# DiplomScheme.net
KiCad netlist of a schematic drawn in Altium Designer
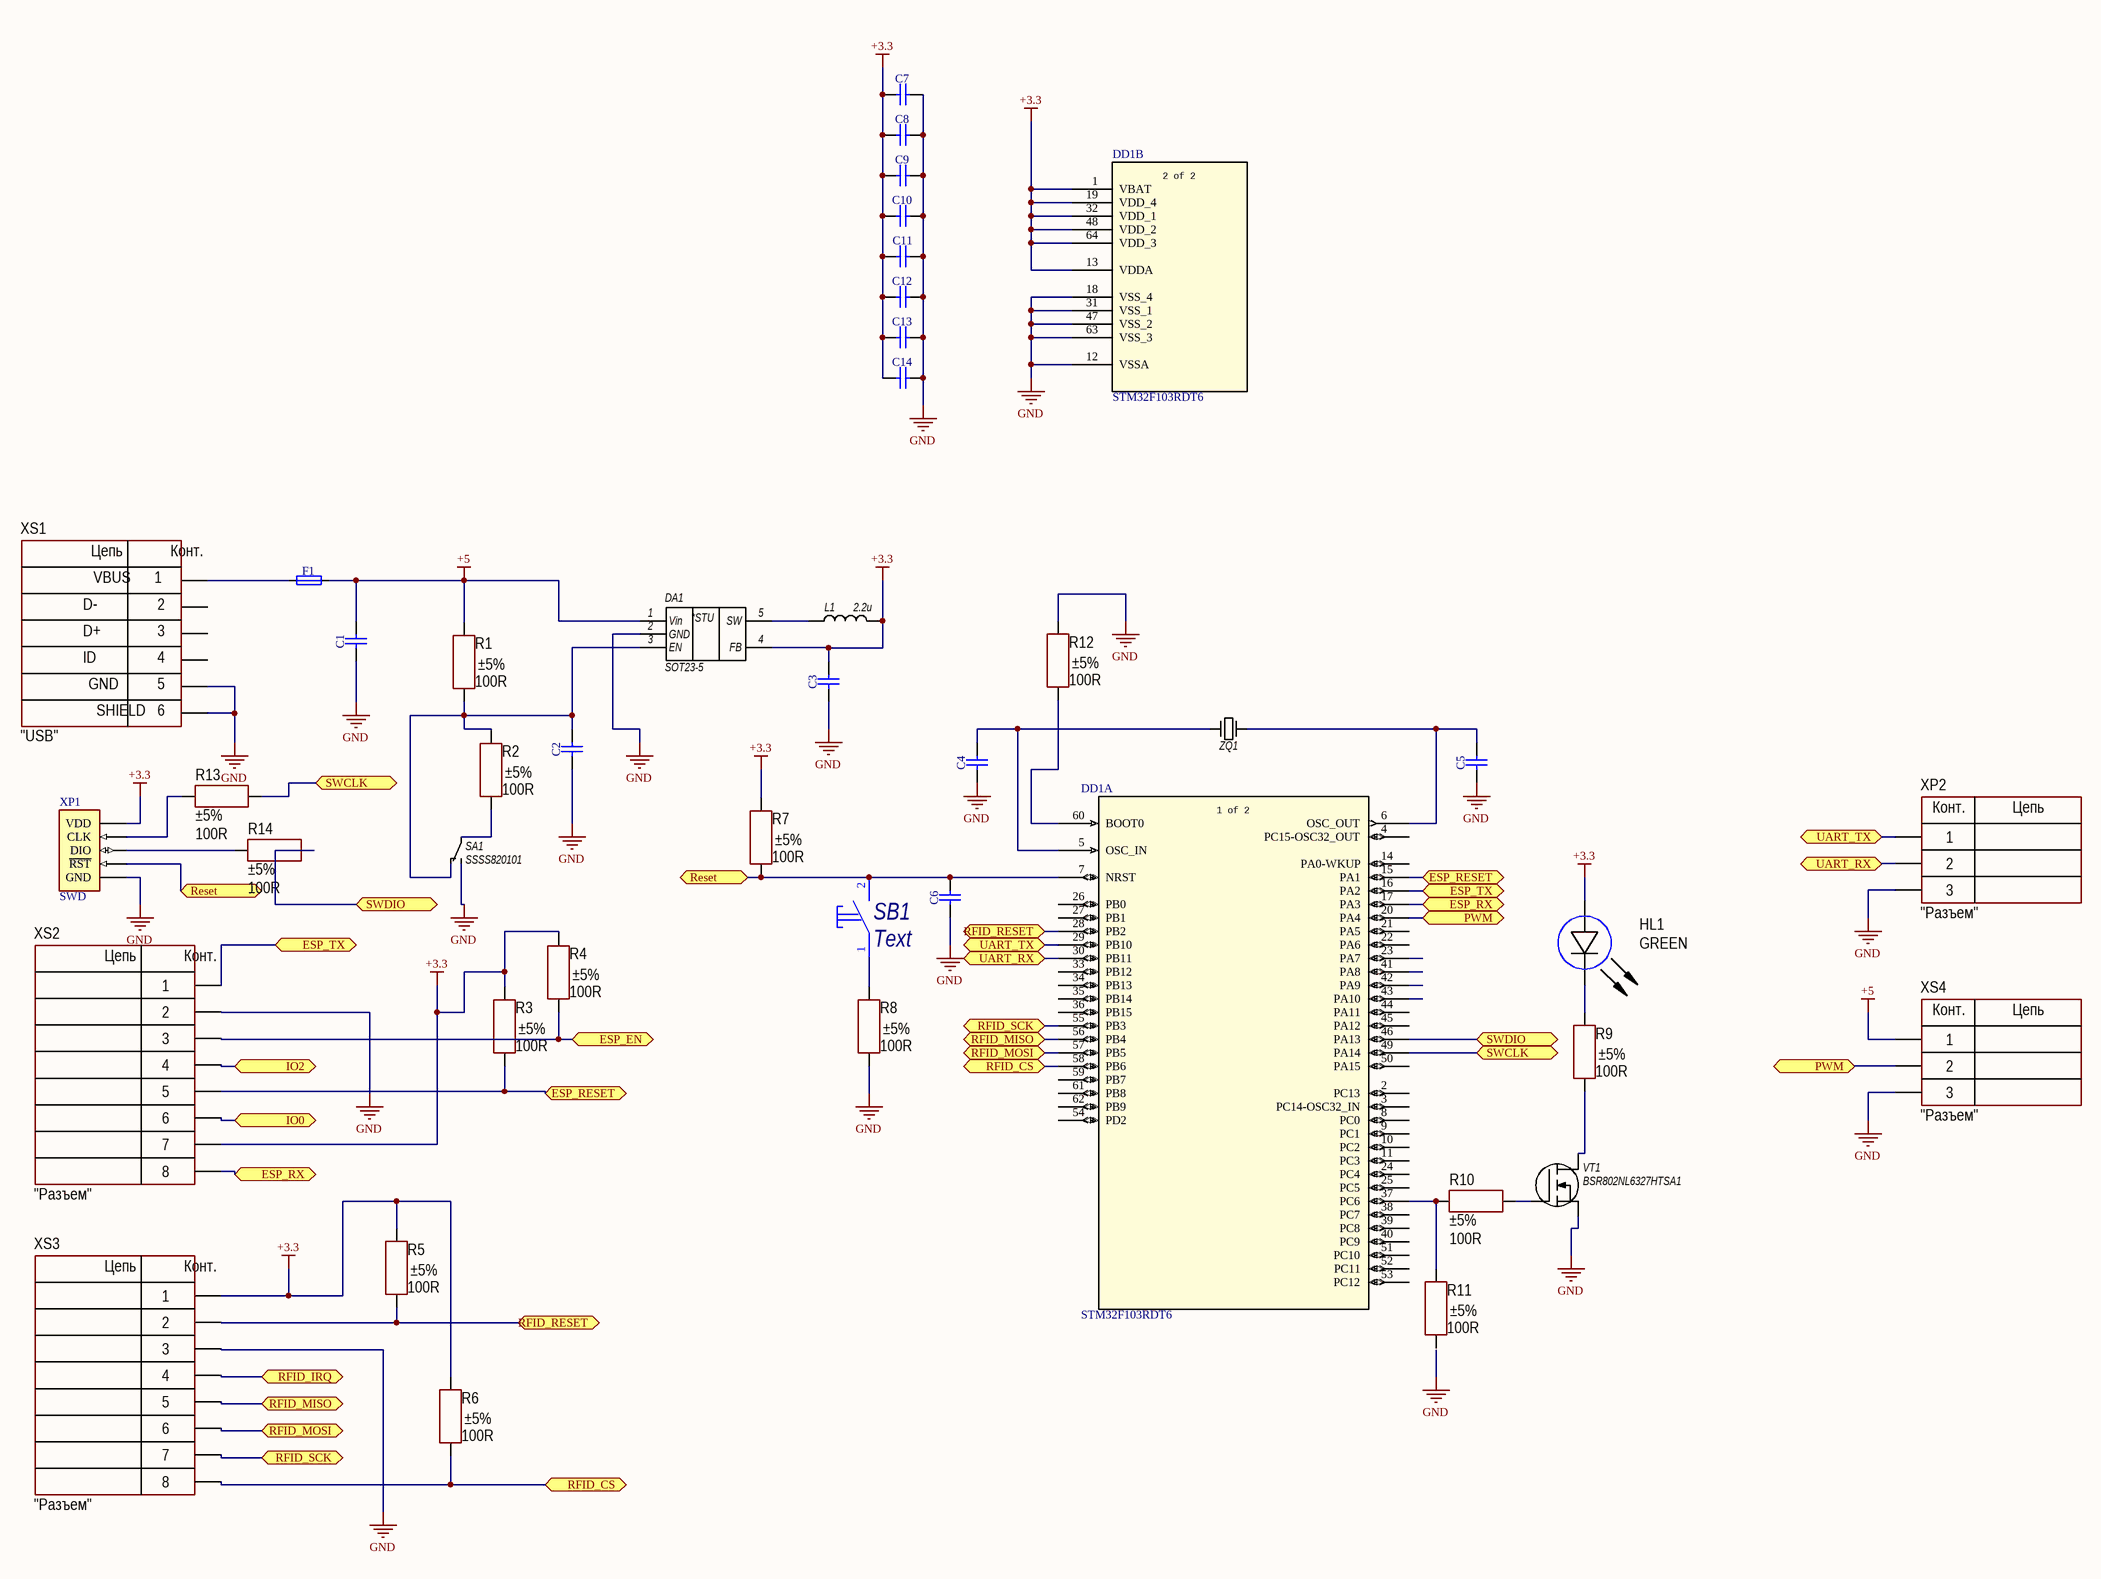
[diagram p0: DiplomScheme.SchDoc]

(export (version "E")
  (design (tool "Eeschema 10.0.6"))
  (components
    (comp (ref "C1")
      (value "47p")
      (footprint "kstd:C0805")
      (description "Non-polarised capacitor")
      (fields
        (field (name "PART NUMBER") "CC1206_47PF_100V_10%_NP0")
        (field (name "VOLTAGE") "100V")
        (field (name "AUTHOR") "CERN DEM JLC")
      )
      (libsource (lib "Capacitors") (part "Capacitor - non polarized"))
    )
    (comp (ref "C2")
      (value "47p")
      (footprint "kstd:C0805")
      (description "Non-polarised capacitor")
      (fields
        (field (name "PART NUMBER") "CC1206_47PF_100V_10%_NP0")
        (field (name "VOLTAGE") "100V")
        (field (name "AUTHOR") "CERN DEM JLC")
      )
      (libsource (lib "Capacitors") (part "Capacitor - non polarized"))
    )
    (comp (ref "C3")
      (value "47p")
      (footprint "kstd:C0805")
      (description "Non-polarised capacitor")
      (fields
        (field (name "PART NUMBER") "CC1206_47PF_100V_10%_NP0")
        (field (name "VOLTAGE") "100V")
        (field (name "AUTHOR") "CERN DEM JLC")
      )
      (libsource (lib "Capacitors") (part "Capacitor - non polarized"))
    )
    (comp (ref "C4")
      (value "47p")
      (footprint "kstd:C0805")
      (description "Non-polarised capacitor")
      (fields
        (field (name "PART NUMBER") "CC1206_47PF_100V_10%_NP0")
        (field (name "VOLTAGE") "100V")
        (field (name "AUTHOR") "CERN DEM JLC")
      )
      (libsource (lib "Capacitors") (part "Capacitor - non polarized"))
    )
    (comp (ref "C5")
      (value "47p")
      (footprint "kstd:C0805")
      (description "Non-polarised capacitor")
      (fields
        (field (name "PART NUMBER") "CC1206_47PF_100V_10%_NP0")
        (field (name "VOLTAGE") "100V")
        (field (name "AUTHOR") "CERN DEM JLC")
      )
      (libsource (lib "Capacitors") (part "Capacitor - non polarized"))
    )
    (comp (ref "C6")
      (value "47p")
      (footprint "kstd:C0805")
      (description "Non-polarised capacitor")
      (fields
        (field (name "PART NUMBER") "CC1206_47PF_100V_10%_NP0")
        (field (name "VOLTAGE") "100V")
        (field (name "AUTHOR") "CERN DEM JLC")
      )
      (libsource (lib "Capacitors") (part "Capacitor - non polarized"))
    )
    (comp (ref "C7")
      (value "47p")
      (footprint "kstd:C0805")
      (description "Non-polarised capacitor")
      (fields
        (field (name "PART NUMBER") "CC1206_47PF_100V_10%_NP0")
        (field (name "VOLTAGE") "100V")
        (field (name "AUTHOR") "CERN DEM JLC")
      )
      (libsource (lib "Capacitors") (part "Capacitor - non polarized"))
    )
    (comp (ref "C8")
      (value "47p")
      (footprint "kstd:C0805")
      (description "Non-polarised capacitor")
      (fields
        (field (name "PART NUMBER") "CC1206_47PF_100V_10%_NP0")
        (field (name "VOLTAGE") "100V")
        (field (name "AUTHOR") "CERN DEM JLC")
      )
      (libsource (lib "Capacitors") (part "Capacitor - non polarized"))
    )
    (comp (ref "C9")
      (value "47p")
      (footprint "kstd:C0805")
      (description "Non-polarised capacitor")
      (fields
        (field (name "PART NUMBER") "CC1206_47PF_100V_10%_NP0")
        (field (name "VOLTAGE") "100V")
        (field (name "AUTHOR") "CERN DEM JLC")
      )
      (libsource (lib "Capacitors") (part "Capacitor - non polarized"))
    )
    (comp (ref "C10")
      (value "47p")
      (footprint "kstd:C0805")
      (description "Non-polarised capacitor")
      (fields
        (field (name "PART NUMBER") "CC1206_47PF_100V_10%_NP0")
        (field (name "VOLTAGE") "100V")
        (field (name "AUTHOR") "CERN DEM JLC")
      )
      (libsource (lib "Capacitors") (part "Capacitor - non polarized"))
    )
    (comp (ref "C11")
      (value "47p")
      (footprint "kstd:C0805")
      (description "Non-polarised capacitor")
      (fields
        (field (name "PART NUMBER") "CC1206_47PF_100V_10%_NP0")
        (field (name "VOLTAGE") "100V")
        (field (name "AUTHOR") "CERN DEM JLC")
      )
      (libsource (lib "Capacitors") (part "Capacitor - non polarized"))
    )
    (comp (ref "C12")
      (value "47p")
      (footprint "kstd:C0805")
      (description "Non-polarised capacitor")
      (fields
        (field (name "PART NUMBER") "CC1206_47PF_100V_10%_NP0")
        (field (name "VOLTAGE") "100V")
        (field (name "AUTHOR") "CERN DEM JLC")
      )
      (libsource (lib "Capacitors") (part "Capacitor - non polarized"))
    )
    (comp (ref "C13")
      (value "47p")
      (footprint "kstd:C0805")
      (description "Non-polarised capacitor")
      (fields
        (field (name "PART NUMBER") "CC1206_47PF_100V_10%_NP0")
        (field (name "VOLTAGE") "100V")
        (field (name "AUTHOR") "CERN DEM JLC")
      )
      (libsource (lib "Capacitors") (part "Capacitor - non polarized"))
    )
    (comp (ref "C14")
      (value "47p")
      (footprint "kstd:C0805")
      (description "Non-polarised capacitor")
      (fields
        (field (name "PART NUMBER") "CC1206_47PF_100V_10%_NP0")
        (field (name "VOLTAGE") "100V")
        (field (name "AUTHOR") "CERN DEM JLC")
      )
      (libsource (lib "Capacitors") (part "Capacitor - non polarized"))
    )
    (comp (ref "DA1")
      (value "SOT23-5")
      (footprint "SOT23-5")
      (description "GOST DC-DC Step-down converter 2.7-5.5 to 3.3V 600mA output")
      (libsource (lib "GOST") (part "LM3671MF-3.3/NOPB"))
    )
    (comp (ref "DD1")
      (value "STM32F103RDT6")
      (footprint "LQFP64-10x10mm")
      (description "No Description Available")
      (fields (field (name "COPYRIGHT") "Copyright (C) 2018 Accelerated Designs. All rights reserved"))
      (libsource (lib "2021-03-14_21-57-24") (part "STM32F103RDT6"))
    )
    (comp (ref "F1")
      (value "0.14A-60V")
      (footprint "FUSRC4632X90N")
      (description "Fuse")
      (fields
        (field (name "PART NUMBER") "FUSR1812_TYCO-miniSMD0114F")
        (field (name "MANUFACTURER") "TYCO ELECTRONICS")
        (field (name "AUTHOR") "CERN DEM JLC")
      )
      (libsource (lib "Eletro-mechanical") (part "Fuse"))
    )
    (comp (ref "HL1")
      (value "~")
      (footprint "LED: 1206R")
      (fields
        (field (name "VALUEMANUFACTURERPARTNUMBER") "LED, *, *, *, -55...+150°C")
        (field (name "COLOR") "GREEN")
      )
      (libsource (lib "Diode") (part "LED_single"))
    )
    (comp (ref "L1")
      (value "2.2u")
      (footprint "kstd:CDRH103R")
      (description "GOST inductive")
      (libsource (lib "GOST") (part "Inductive"))
    )
    (comp (ref "R1")
      (value "100R")
      (footprint "kstd:R0805")
      (fields
        (field (name "MANUFACTURER") "Yageo")
        (field (name "PARTNUMBER") "RC1206JR-07100RL")
        (field (name "VALUEMANUFACTURERPARTNUMBER") "Resistor film, 100R, ±5%, 1206, 0.25W, -55...+125°C")
        (field (name "TOLERANCE") "±5%")
      )
      (libsource (lib "Resistor") (part "Resistor_1206"))
    )
    (comp (ref "R2")
      (value "100R")
      (footprint "kstd:R0805")
      (fields
        (field (name "MANUFACTURER") "Yageo")
        (field (name "PARTNUMBER") "RC1206JR-07100RL")
        (field (name "VALUEMANUFACTURERPARTNUMBER") "Resistor film, 100R, ±5%, 1206, 0.25W, -55...+125°C")
        (field (name "TOLERANCE") "±5%")
      )
      (libsource (lib "Resistor") (part "Resistor_1206"))
    )
    (comp (ref "R3")
      (value "100R")
      (footprint "kstd:R0805")
      (fields
        (field (name "MANUFACTURER") "Yageo")
        (field (name "PARTNUMBER") "RC1206JR-07100RL")
        (field (name "VALUEMANUFACTURERPARTNUMBER") "Resistor film, 100R, ±5%, 1206, 0.25W, -55...+125°C")
        (field (name "TOLERANCE") "±5%")
      )
      (libsource (lib "Resistor") (part "Resistor_1206"))
    )
    (comp (ref "R4")
      (value "100R")
      (footprint "kstd:R0805")
      (fields
        (field (name "MANUFACTURER") "Yageo")
        (field (name "PARTNUMBER") "RC1206JR-07100RL")
        (field (name "VALUEMANUFACTURERPARTNUMBER") "Resistor film, 100R, ±5%, 1206, 0.25W, -55...+125°C")
        (field (name "TOLERANCE") "±5%")
      )
      (libsource (lib "Resistor") (part "Resistor_1206"))
    )
    (comp (ref "R5")
      (value "100R")
      (footprint "kstd:R0805")
      (fields
        (field (name "MANUFACTURER") "Yageo")
        (field (name "PARTNUMBER") "RC1206JR-07100RL")
        (field (name "VALUEMANUFACTURERPARTNUMBER") "Resistor film, 100R, ±5%, 1206, 0.25W, -55...+125°C")
        (field (name "TOLERANCE") "±5%")
      )
      (libsource (lib "Resistor") (part "Resistor_1206"))
    )
    (comp (ref "R6")
      (value "100R")
      (footprint "kstd:R0805")
      (fields
        (field (name "MANUFACTURER") "Yageo")
        (field (name "PARTNUMBER") "RC1206JR-07100RL")
        (field (name "VALUEMANUFACTURERPARTNUMBER") "Resistor film, 100R, ±5%, 1206, 0.25W, -55...+125°C")
        (field (name "TOLERANCE") "±5%")
      )
      (libsource (lib "Resistor") (part "Resistor_1206"))
    )
    (comp (ref "R7")
      (value "100R")
      (footprint "kstd:R0805")
      (fields
        (field (name "MANUFACTURER") "Yageo")
        (field (name "PARTNUMBER") "RC1206JR-07100RL")
        (field (name "VALUEMANUFACTURERPARTNUMBER") "Resistor film, 100R, ±5%, 1206, 0.25W, -55...+125°C")
        (field (name "TOLERANCE") "±5%")
      )
      (libsource (lib "Resistor") (part "Resistor_1206"))
    )
    (comp (ref "R8")
      (value "100R")
      (footprint "kstd:R0805")
      (fields
        (field (name "MANUFACTURER") "Yageo")
        (field (name "PARTNUMBER") "RC1206JR-07100RL")
        (field (name "VALUEMANUFACTURERPARTNUMBER") "Resistor film, 100R, ±5%, 1206, 0.25W, -55...+125°C")
        (field (name "TOLERANCE") "±5%")
      )
      (libsource (lib "Resistor") (part "Resistor_1206"))
    )
    (comp (ref "R9")
      (value "100R")
      (footprint "kstd:R0805")
      (fields
        (field (name "MANUFACTURER") "Yageo")
        (field (name "PARTNUMBER") "RC1206JR-07100RL")
        (field (name "VALUEMANUFACTURERPARTNUMBER") "Resistor film, 100R, ±5%, 1206, 0.25W, -55...+125°C")
        (field (name "TOLERANCE") "±5%")
      )
      (libsource (lib "Resistor") (part "Resistor_1206"))
    )
    (comp (ref "R10")
      (value "100R")
      (footprint "kstd:R0805")
      (fields
        (field (name "MANUFACTURER") "Yageo")
        (field (name "PARTNUMBER") "RC1206JR-07100RL")
        (field (name "VALUEMANUFACTURERPARTNUMBER") "Resistor film, 100R, ±5%, 1206, 0.25W, -55...+125°C")
        (field (name "TOLERANCE") "±5%")
      )
      (libsource (lib "") (part "Resistor_1206_1"))
    )
    (comp (ref "R11")
      (value "100R")
      (footprint "kstd:R0805")
      (fields
        (field (name "MANUFACTURER") "Yageo")
        (field (name "PARTNUMBER") "RC1206JR-07100RL")
        (field (name "VALUEMANUFACTURERPARTNUMBER") "Resistor film, 100R, ±5%, 1206, 0.25W, -55...+125°C")
        (field (name "TOLERANCE") "±5%")
      )
      (libsource (lib "Resistor") (part "Resistor_1206"))
    )
    (comp (ref "R12")
      (value "100R")
      (footprint "kstd:R0805")
      (fields
        (field (name "MANUFACTURER") "Yageo")
        (field (name "PARTNUMBER") "RC1206JR-07100RL")
        (field (name "VALUEMANUFACTURERPARTNUMBER") "Resistor film, 100R, ±5%, 1206, 0.25W, -55...+125°C")
        (field (name "TOLERANCE") "±5%")
      )
      (libsource (lib "Resistor") (part "Resistor_1206"))
    )
    (comp (ref "R13")
      (value "100R")
      (footprint "kstd:R0805")
      (fields
        (field (name "MANUFACTURER") "Yageo")
        (field (name "PARTNUMBER") "RC1206JR-07100RL")
        (field (name "VALUEMANUFACTURERPARTNUMBER") "Resistor film, 100R, ±5%, 1206, 0.25W, -55...+125°C")
        (field (name "TOLERANCE") "±5%")
      )
      (libsource (lib "") (part "Resistor_1206_1"))
    )
    (comp (ref "R14")
      (value "100R")
      (footprint "kstd:R0805")
      (fields
        (field (name "MANUFACTURER") "Yageo")
        (field (name "PARTNUMBER") "RC1206JR-07100RL")
        (field (name "VALUEMANUFACTURERPARTNUMBER") "Resistor film, 100R, ±5%, 1206, 0.25W, -55...+125°C")
        (field (name "TOLERANCE") "±5%")
      )
      (libsource (lib "") (part "Resistor_1206_1"))
    )
    (comp (ref "SA1")
      (value "SSSS820101")
      (footprint "SSSS820101")
      (description "GOST Button Perekluchatel")
      (libsource (lib "GOST") (part "Button_Perekluchatel"))
    )
    (comp (ref "SB1")
      (value "Text")
      (footprint "ПКн159-3_4-Series")
      (fields (field (name "PART NUMBER") "ПКн159-3") (field (name "PUBLISHER") "Andrew Danich"))
      (libsource (lib "Lib_GOST") (part "BT-01x-01p"))
    )
    (comp (ref "VT1")
      (value "BSR802NL6327HTSA1")
      (footprint "kilb:SOT23")
      (description "GOST MOSFET N-channel transistor")
      (libsource (lib "GOST") (part "MOSFET_N"))
    )
    (comp (ref "XP1")
      (value "SWD")
      (footprint "kconn:PLS5R")
      (description "Serial Wire Debugging")
      (fields (field (name "PUBLISHER") "Kernel Laboratory"))
      (libsource (lib "kconn") (part "SWD"))
    )
    (comp (ref "XP2")
      (value "~")
      (footprint "kconn:PLS3R")
      (fields
        (field (name "MANUFACTURER") "Connfly")
        (field (name "VALUEMANUFACTURERPARTNUMBER") "Connector, 3pin, 2.54mm, 500VAC, 3A")
        (field (name "PARTNUMBER") "PLS-3")
        (field (name "COMMENTTEXT") "\"Разъем\"")
      )
      (libsource (lib "Connector") (part "PLS-3"))
    )
    (comp (ref "XS1")
      (value "~")
      (footprint "CON: USB micro-A (ZX62-B-5PA)")
      (fields
        (field (name "MANUFACTURER") "Hirose Electric")
        (field (name "VALUEMANUFACTURERPARTNUMBER") "USB micro B")
        (field (name "PARTNUMBER") "ZX62-B-5PA")
        (field (name "COMMENTTEXT") "\"USB\"")
      )
      (libsource (lib "Connector") (part "Connector_USB_micro_B"))
    )
    (comp (ref "XS2")
      (value "~")
      (footprint "CON: PBD-8")
      (fields
        (field (name "MANUFACTURER") "Connfly")
        (field (name "VALUEMANUFACTURERPARTNUMBER") "Connector, 8pin, 2.54mm, 500VAC, 3A")
        (field (name "PARTNUMBER") "PBD-8")
        (field (name "COMMENTTEXT") "\"Разъем\"")
      )
      (libsource (lib "Connector") (part "PBD-8"))
    )
    (comp (ref "XS3")
      (value "~")
      (footprint "CON: PBS-8")
      (fields
        (field (name "MANUFACTURER") "Connfly")
        (field (name "VALUEMANUFACTURERPARTNUMBER") "Connector, 8pin, 2.54mm, 500VAC, 3A")
        (field (name "PARTNUMBER") "PBS-8")
        (field (name "COMMENTTEXT") "\"Разъем\"")
      )
      (libsource (lib "Connector") (part "PBS-8"))
    )
    (comp (ref "XS4")
      (value "~")
      (footprint "CON: DG350-3.5-03P")
      (fields
        (field (name "MANUFACTURER") "Degson")
        (field (name "VALUEMANUFACTURERPARTNUMBER") "Terminal connector, 3pin, 3.5mm, 300VAC, 10A")
        (field (name "PARTNUMBER") "DG350-3.5-03P-14")
        (field (name "COMMENTTEXT") "\"Разъем\"")
      )
      (libsource (lib "Connector") (part "Connector_terminal_3pin"))
    )
    (comp (ref "ZQ1")
      (value "QSMD3.2x2.5x0.8")
      (footprint "QSMD3.2x2.5x0.8")
      (description "GOST Quartz")
      (libsource (lib "GOST") (part "Quartz"))
    )
  )
  (nets
    (net (code "1") (name "+3.3") (class "Default")
      (node (ref "C10") (pin "1") (pinfunction "1_1") (pintype "passive"))
      (node (ref "C11") (pin "1") (pinfunction "1_1") (pintype "passive"))
      (node (ref "C12") (pin "1") (pinfunction "1_1") (pintype "passive"))
      (node (ref "C13") (pin "1") (pinfunction "1_1") (pintype "passive"))
      (node (ref "C14") (pin "1") (pinfunction "1_1") (pintype "passive"))
      (node (ref "C3") (pin "2") (pinfunction "2_2") (pintype "passive"))
      (node (ref "C7") (pin "1") (pinfunction "1_1") (pintype "passive"))
      (node (ref "C8") (pin "1") (pinfunction "1_1") (pintype "passive"))
      (node (ref "C9") (pin "1") (pinfunction "1_1") (pintype "passive"))
      (node (ref "DA1") (pin "4") (pinfunction "FB_4") (pintype "passive"))
      (node (ref "DD1") (pin "1") (pinfunction "VBAT_1") (pintype "power_in"))
      (node (ref "DD1") (pin "13") (pinfunction "VDDA_13") (pintype "power_in"))
      (node (ref "DD1") (pin "19") (pinfunction "VDD_4_19") (pintype "power_in"))
      (node (ref "DD1") (pin "32") (pinfunction "VDD_1_32") (pintype "power_in"))
      (node (ref "DD1") (pin "48") (pinfunction "VDD_2_48") (pintype "power_in"))
      (node (ref "DD1") (pin "64") (pinfunction "VDD_3_64") (pintype "power_in"))
      (node (ref "HL1") (pin "1") (pinfunction "A_1") (pintype "passive"))
      (node (ref "L1") (pin "2") (pinfunction "2_2") (pintype "passive"))
      (node (ref "R3") (pin "2") (pinfunction "2_2") (pintype "passive"))
      (node (ref "R4") (pin "2") (pinfunction "2_2") (pintype "passive"))
      (node (ref "R5") (pin "2") (pinfunction "2_2") (pintype "passive"))
      (node (ref "R6") (pin "2") (pinfunction "2_2") (pintype "passive"))
      (node (ref "R7") (pin "2") (pinfunction "2_2") (pintype "passive"))
      (node (ref "XP1") (pin "VDD") (pinfunction "VDD_VDD") (pintype "power_in"))
      (node (ref "XS2") (pin "7") (pinfunction "7_7") (pintype "power_in"))
      (node (ref "XS3") (pin "1") (pinfunction "1_1") (pintype "passive"))
    )
    (net (code "2") (name "+5") (class "Default")
      (node (ref "C1") (pin "2") (pinfunction "2_2") (pintype "passive"))
      (node (ref "DA1") (pin "1") (pinfunction "Vin_1") (pintype "passive"))
      (node (ref "F1") (pin "2") (pinfunction "2_2") (pintype "passive"))
      (node (ref "R1") (pin "2") (pinfunction "2_2") (pintype "passive"))
      (node (ref "XS4") (pin "1") (pinfunction "1_1") (pintype "passive"))
    )
    (net (code "3") (name "/ESP_EN") (class "Default")
      (node (ref "R4") (pin "1") (pinfunction "1_1") (pintype "passive"))
      (node (ref "XS2") (pin "3") (pinfunction "3_3") (pintype "power_in"))
    )
    (net (code "4") (name "/ESP_RESET") (class "Default")
      (node (ref "DD1") (pin "15") (pinfunction "PA1_15") (pintype "bidirectional"))
      (node (ref "R3") (pin "1") (pinfunction "1_1") (pintype "passive"))
      (node (ref "XS2") (pin "5") (pinfunction "5_5") (pintype "power_in"))
    )
    (net (code "5") (name "/ESP_RX") (class "Default")
      (node (ref "DD1") (pin "17") (pinfunction "PA3_17") (pintype "bidirectional"))
      (node (ref "XS2") (pin "8") (pinfunction "8_8") (pintype "power_in"))
    )
    (net (code "6") (name "/ESP_TX") (class "Default")
      (node (ref "DD1") (pin "16") (pinfunction "PA2_16") (pintype "bidirectional"))
      (node (ref "XS2") (pin "1") (pinfunction "1_1") (pintype "passive"))
    )
    (net (code "7") (name "/IO0") (class "Default")
      (node (ref "XS2") (pin "6") (pinfunction "6_6") (pintype "power_in"))
    )
    (net (code "8") (name "/IO2") (class "Default")
      (node (ref "XS2") (pin "4") (pinfunction "4_4") (pintype "power_in"))
    )
    (net (code "9") (name "/PWM") (class "Default")
      (node (ref "DD1") (pin "20") (pinfunction "PA4_20") (pintype "bidirectional"))
      (node (ref "XS4") (pin "2") (pinfunction "2_2") (pintype "passive"))
    )
    (net (code "10") (name "/RFID_CS") (class "Default")
      (node (ref "DD1") (pin "58") (pinfunction "PB6_58") (pintype "bidirectional"))
      (node (ref "R6") (pin "1") (pinfunction "1_1") (pintype "passive"))
      (node (ref "XS3") (pin "8") (pinfunction "8_8") (pintype "power_in"))
    )
    (net (code "11") (name "/RFID_IRQ") (class "Default")
      (node (ref "XS3") (pin "4") (pinfunction "4_4") (pintype "power_in"))
    )
    (net (code "12") (name "/RFID_MISO") (class "Default")
      (node (ref "DD1") (pin "56") (pinfunction "PB4_56") (pintype "bidirectional"))
      (node (ref "XS3") (pin "5") (pinfunction "5_5") (pintype "power_in"))
    )
    (net (code "13") (name "/RFID_MOSI") (class "Default")
      (node (ref "DD1") (pin "57") (pinfunction "PB5_57") (pintype "bidirectional"))
      (node (ref "XS3") (pin "6") (pinfunction "6_6") (pintype "power_in"))
    )
    (net (code "14") (name "/RFID_RESET") (class "Default")
      (node (ref "DD1") (pin "28") (pinfunction "PB2_28") (pintype "bidirectional"))
      (node (ref "R5") (pin "1") (pinfunction "1_1") (pintype "passive"))
      (node (ref "XS3") (pin "2") (pinfunction "2_2") (pintype "passive"))
    )
    (net (code "15") (name "/RFID_SCK") (class "Default")
      (node (ref "DD1") (pin "55") (pinfunction "PB3_55") (pintype "bidirectional"))
      (node (ref "XS3") (pin "7") (pinfunction "7_7") (pintype "power_in"))
    )
    (net (code "16") (name "/Reset") (class "Default")
      (node (ref "C6") (pin "2") (pinfunction "2_2") (pintype "passive"))
      (node (ref "DD1") (pin "7") (pinfunction "NRST_7") (pintype "bidirectional"))
      (node (ref "R7") (pin "1") (pinfunction "1_1") (pintype "passive"))
      (node (ref "SB1") (pin "2") (pintype "passive"))
      (node (ref "XP1") (pin "NRST") (pinfunction "RST_NRST") (pintype "input"))
    )
    (net (code "17") (name "/SWCLK") (class "Default")
      (node (ref "DD1") (pin "49") (pinfunction "PA14_49") (pintype "bidirectional"))
      (node (ref "R13") (pin "1") (pinfunction "1_1") (pintype "passive"))
    )
    (net (code "18") (name "/SWDIO") (class "Default")
      (node (ref "DD1") (pin "46") (pinfunction "PA13_46") (pintype "bidirectional"))
      (node (ref "R14") (pin "1") (pinfunction "1_1") (pintype "passive"))
    )
    (net (code "19") (name "/UART_RX") (class "Default")
      (node (ref "DD1") (pin "30") (pinfunction "PB11_30") (pintype "bidirectional"))
      (node (ref "XP2") (pin "2") (pinfunction "2_2") (pintype "passive"))
    )
    (net (code "20") (name "/UART_TX") (class "Default")
      (node (ref "DD1") (pin "29") (pinfunction "PB10_29") (pintype "bidirectional"))
      (node (ref "XP2") (pin "1") (pinfunction "1_1") (pintype "passive"))
    )
    (net (code "21") (name "GND") (class "Default")
      (node (ref "C1") (pin "1") (pinfunction "1_1") (pintype "passive"))
      (node (ref "C10") (pin "2") (pinfunction "2_2") (pintype "passive"))
      (node (ref "C11") (pin "2") (pinfunction "2_2") (pintype "passive"))
      (node (ref "C12") (pin "2") (pinfunction "2_2") (pintype "passive"))
      (node (ref "C13") (pin "2") (pinfunction "2_2") (pintype "passive"))
      (node (ref "C14") (pin "2") (pinfunction "2_2") (pintype "passive"))
      (node (ref "C2") (pin "1") (pinfunction "1_1") (pintype "passive"))
      (node (ref "C3") (pin "1") (pinfunction "1_1") (pintype "passive"))
      (node (ref "C4") (pin "1") (pinfunction "1_1") (pintype "passive"))
      (node (ref "C5") (pin "1") (pinfunction "1_1") (pintype "passive"))
      (node (ref "C6") (pin "1") (pinfunction "1_1") (pintype "passive"))
      (node (ref "C7") (pin "2") (pinfunction "2_2") (pintype "passive"))
      (node (ref "C8") (pin "2") (pinfunction "2_2") (pintype "passive"))
      (node (ref "C9") (pin "2") (pinfunction "2_2") (pintype "passive"))
      (node (ref "DA1") (pin "2") (pinfunction "GND_2") (pintype "passive"))
      (node (ref "DD1") (pin "12") (pinfunction "VSSA_12") (pintype "power_in"))
      (node (ref "DD1") (pin "18") (pinfunction "VSS_4_18") (pintype "power_in"))
      (node (ref "DD1") (pin "31") (pinfunction "VSS_1_31") (pintype "power_in"))
      (node (ref "DD1") (pin "47") (pinfunction "VSS_2_47") (pintype "power_in"))
      (node (ref "DD1") (pin "63") (pinfunction "VSS_3_63") (pintype "power_in"))
      (node (ref "R12") (pin "2") (pinfunction "2_2") (pintype "passive"))
      (node (ref "R8") (pin "1") (pinfunction "1_1") (pintype "passive"))
      (node (ref "SA1") (pin "1") (pinfunction "1_1") (pintype "passive"))
      (node (ref "VT1") (pin "2") (pinfunction "Source_2") (pintype "passive"))
      (node (ref "XP1") (pin "GND") (pinfunction "GND_GND") (pintype "power_in"))
      (node (ref "XP2") (pin "3") (pinfunction "3_3") (pintype "power_in"))
      (node (ref "XS1") (pin "0") (pinfunction "0_0") (pintype "passive"))
      (node (ref "XS1") (pin "5") (pinfunction "5_5") (pintype "passive"))
      (node (ref "XS2") (pin "2") (pinfunction "2_2") (pintype "passive"))
      (node (ref "XS3") (pin "3") (pinfunction "3_3") (pintype "power_in"))
      (node (ref "XS4") (pin "3") (pinfunction "3_3") (pintype "power_in"))
    )
    (net (code "22") (name "Net-(DA1-EN)") (class "Default")
      (node (ref "C2") (pin "2") (pinfunction "2_2") (pintype "passive"))
      (node (ref "DA1") (pin "3") (pinfunction "EN_3") (pintype "passive"))
      (node (ref "R1") (pin "1") (pinfunction "1_1") (pintype "passive"))
      (node (ref "R2") (pin "2") (pinfunction "2_2") (pintype "passive"))
      (node (ref "SA1") (pin "3") (pinfunction "3_3") (pintype "passive"))
    )
    (net (code "23") (name "Net-(DA1-SW)") (class "Default")
      (node (ref "DA1") (pin "5") (pinfunction "SW_5") (pintype "passive"))
      (node (ref "L1") (pin "1") (pinfunction "1_1") (pintype "passive"))
    )
    (net (code "24") (name "Net-(DD1A-BOOT0)") (class "Default")
      (node (ref "DD1") (pin "60") (pinfunction "BOOT0_60") (pintype "input"))
      (node (ref "R12") (pin "1") (pinfunction "1_1") (pintype "passive"))
    )
    (net (code "25") (name "Net-(DD1A-OSC_IN)") (class "Default")
      (node (ref "C4") (pin "2") (pinfunction "2_2") (pintype "passive"))
      (node (ref "DD1") (pin "5") (pinfunction "OSC_IN_5") (pintype "input"))
      (node (ref "ZQ1") (pin "3") (pinfunction "3_3") (pintype "passive"))
    )
    (net (code "26") (name "Net-(DD1A-OSC_OUT)") (class "Default")
      (node (ref "C5") (pin "2") (pinfunction "2_2") (pintype "passive"))
      (node (ref "DD1") (pin "6") (pinfunction "OSC_OUT_6") (pintype "output"))
      (node (ref "ZQ1") (pin "1") (pinfunction "1_1") (pintype "passive"))
    )
    (net (code "27") (name "Net-(DD1A-PC6)") (class "Default")
      (node (ref "DD1") (pin "37") (pinfunction "PC6_37") (pintype "bidirectional"))
      (node (ref "R10") (pin "2") (pinfunction "2_2") (pintype "passive"))
      (node (ref "R11") (pin "2") (pinfunction "2_2") (pintype "passive"))
    )
    (net (code "28") (name "Net-(F1-Pad1)") (class "Default")
      (node (ref "F1") (pin "1") (pinfunction "1_1") (pintype "passive"))
      (node (ref "XS1") (pin "1") (pintype "passive"))
    )
    (net (code "29") (name "Net-(HL1-C)") (class "Default")
      (node (ref "HL1") (pin "2") (pinfunction "C_2") (pintype "passive"))
      (node (ref "R9") (pin "2") (pinfunction "2_2") (pintype "passive"))
    )
    (net (code "30") (name "Net-(R2-Pad1)") (class "Default")
      (node (ref "R2") (pin "1") (pinfunction "1_1") (pintype "passive"))
      (node (ref "SA1") (pin "2") (pinfunction "2_2") (pintype "passive"))
    )
    (net (code "31") (name "Net-(R8-Pad2)") (class "Default")
      (node (ref "R8") (pin "2") (pinfunction "2_2") (pintype "passive"))
      (node (ref "SB1") (pin "1") (pintype "passive"))
    )
    (net (code "32") (name "Net-(R13-Pad2)") (class "Default")
      (node (ref "R13") (pin "2") (pinfunction "2_2") (pintype "passive"))
      (node (ref "XP1") (pin "CLK") (pinfunction "CLK_CLK") (pintype "input"))
    )
    (net (code "33") (name "Net-(R14-Pad2)") (class "Default")
      (node (ref "R14") (pin "2") (pinfunction "2_2") (pintype "passive"))
      (node (ref "XP1") (pin "DIO") (pinfunction "DIO_DIO") (pintype "bidirectional"))
    )
    (net (code "34") (name "Net-(VT1-Drain)") (class "Default")
      (node (ref "R9") (pin "1") (pinfunction "1_1") (pintype "passive"))
      (node (ref "VT1") (pin "3") (pinfunction "Drain_3") (pintype "passive"))
    )
    (net (code "35") (name "Net-(VT1-Gate)") (class "Default")
      (node (ref "R10") (pin "1") (pinfunction "1_1") (pintype "passive"))
      (node (ref "VT1") (pin "1") (pinfunction "Gate_1") (pintype "passive"))
    )
    (net (code "36") (name "unconnected-(DD1A-PA0-WKUP-Pad14)") (class "Default")
      (node (ref "DD1") (pin "14") (pinfunction "PA0-WKUP_14") (pintype "bidirectional"))
    )
    (net (code "37") (name "unconnected-(DD1A-PA5-Pad21)") (class "Default")
      (node (ref "DD1") (pin "21") (pinfunction "PA5_21") (pintype "bidirectional"))
    )
    (net (code "38") (name "unconnected-(DD1A-PA6-Pad22)") (class "Default")
      (node (ref "DD1") (pin "22") (pinfunction "PA6_22") (pintype "bidirectional"))
    )
    (net (code "39") (name "unconnected-(DD1A-PA7-Pad23)") (class "Default")
      (node (ref "DD1") (pin "23") (pinfunction "PA7_23") (pintype "bidirectional"))
    )
    (net (code "40") (name "unconnected-(DD1A-PA8-Pad41)") (class "Default")
      (node (ref "DD1") (pin "41") (pinfunction "PA8_41") (pintype "bidirectional"))
    )
    (net (code "41") (name "unconnected-(DD1A-PA9-Pad42)") (class "Default")
      (node (ref "DD1") (pin "42") (pinfunction "PA9_42") (pintype "bidirectional"))
    )
    (net (code "42") (name "unconnected-(DD1A-PA10-Pad43)") (class "Default")
      (node (ref "DD1") (pin "43") (pinfunction "PA10_43") (pintype "bidirectional"))
    )
    (net (code "43") (name "unconnected-(DD1A-PA11-Pad44)") (class "Default")
      (node (ref "DD1") (pin "44") (pinfunction "PA11_44") (pintype "bidirectional"))
    )
    (net (code "44") (name "unconnected-(DD1A-PA12-Pad45)") (class "Default")
      (node (ref "DD1") (pin "45") (pinfunction "PA12_45") (pintype "bidirectional"))
    )
    (net (code "45") (name "unconnected-(DD1A-PA15-Pad50)") (class "Default")
      (node (ref "DD1") (pin "50") (pinfunction "PA15_50") (pintype "bidirectional"))
    )
    (net (code "46") (name "unconnected-(DD1A-PB0-Pad26)") (class "Default")
      (node (ref "DD1") (pin "26") (pinfunction "PB0_26") (pintype "bidirectional"))
    )
    (net (code "47") (name "unconnected-(DD1A-PB1-Pad27)") (class "Default")
      (node (ref "DD1") (pin "27") (pinfunction "PB1_27") (pintype "bidirectional"))
    )
    (net (code "48") (name "unconnected-(DD1A-PB7-Pad59)") (class "Default")
      (node (ref "DD1") (pin "59") (pinfunction "PB7_59") (pintype "bidirectional"))
    )
    (net (code "49") (name "unconnected-(DD1A-PB8-Pad61)") (class "Default")
      (node (ref "DD1") (pin "61") (pinfunction "PB8_61") (pintype "bidirectional"))
    )
    (net (code "50") (name "unconnected-(DD1A-PB9-Pad62)") (class "Default")
      (node (ref "DD1") (pin "62") (pinfunction "PB9_62") (pintype "bidirectional"))
    )
    (net (code "51") (name "unconnected-(DD1A-PB12-Pad33)") (class "Default")
      (node (ref "DD1") (pin "33") (pinfunction "PB12_33") (pintype "bidirectional"))
    )
    (net (code "52") (name "unconnected-(DD1A-PB13-Pad34)") (class "Default")
      (node (ref "DD1") (pin "34") (pinfunction "PB13_34") (pintype "bidirectional"))
    )
    (net (code "53") (name "unconnected-(DD1A-PB14-Pad35)") (class "Default")
      (node (ref "DD1") (pin "35") (pinfunction "PB14_35") (pintype "bidirectional"))
    )
    (net (code "54") (name "unconnected-(DD1A-PB15-Pad36)") (class "Default")
      (node (ref "DD1") (pin "36") (pinfunction "PB15_36") (pintype "bidirectional"))
    )
    (net (code "55") (name "unconnected-(DD1A-PC0-Pad8)") (class "Default")
      (node (ref "DD1") (pin "8") (pinfunction "PC0_8") (pintype "bidirectional"))
    )
    (net (code "56") (name "unconnected-(DD1A-PC1-Pad9)") (class "Default")
      (node (ref "DD1") (pin "9") (pinfunction "PC1_9") (pintype "bidirectional"))
    )
    (net (code "57") (name "unconnected-(DD1A-PC2-Pad10)") (class "Default")
      (node (ref "DD1") (pin "10") (pinfunction "PC2_10") (pintype "bidirectional"))
    )
    (net (code "58") (name "unconnected-(DD1A-PC3-Pad11)") (class "Default")
      (node (ref "DD1") (pin "11") (pinfunction "PC3_11") (pintype "bidirectional"))
    )
    (net (code "59") (name "unconnected-(DD1A-PC4-Pad24)") (class "Default")
      (node (ref "DD1") (pin "24") (pinfunction "PC4_24") (pintype "bidirectional"))
    )
    (net (code "60") (name "unconnected-(DD1A-PC5-Pad25)") (class "Default")
      (node (ref "DD1") (pin "25") (pinfunction "PC5_25") (pintype "bidirectional"))
    )
    (net (code "61") (name "unconnected-(DD1A-PC7-Pad38)") (class "Default")
      (node (ref "DD1") (pin "38") (pinfunction "PC7_38") (pintype "bidirectional"))
    )
    (net (code "62") (name "unconnected-(DD1A-PC8-Pad39)") (class "Default")
      (node (ref "DD1") (pin "39") (pinfunction "PC8_39") (pintype "bidirectional"))
    )
    (net (code "63") (name "unconnected-(DD1A-PC9-Pad40)") (class "Default")
      (node (ref "DD1") (pin "40") (pinfunction "PC9_40") (pintype "bidirectional"))
    )
    (net (code "64") (name "unconnected-(DD1A-PC10-Pad51)") (class "Default")
      (node (ref "DD1") (pin "51") (pinfunction "PC10_51") (pintype "bidirectional"))
    )
    (net (code "65") (name "unconnected-(DD1A-PC11-Pad52)") (class "Default")
      (node (ref "DD1") (pin "52") (pinfunction "PC11_52") (pintype "bidirectional"))
    )
    (net (code "66") (name "unconnected-(DD1A-PC12-Pad53)") (class "Default")
      (node (ref "DD1") (pin "53") (pinfunction "PC12_53") (pintype "bidirectional"))
    )
    (net (code "67") (name "unconnected-(DD1A-PC13-Pad2)") (class "Default")
      (node (ref "DD1") (pin "2") (pinfunction "PC13_2") (pintype "bidirectional"))
    )
    (net (code "68") (name "unconnected-(DD1A-PC14-OSC32_IN-Pad3)") (class "Default")
      (node (ref "DD1") (pin "3") (pinfunction "PC14-OSC32_IN_3") (pintype "bidirectional"))
    )
    (net (code "69") (name "unconnected-(DD1A-PC15-OSC32_OUT-Pad4)") (class "Default")
      (node (ref "DD1") (pin "4") (pinfunction "PC15-OSC32_OUT_4") (pintype "bidirectional"))
    )
    (net (code "70") (name "unconnected-(DD1A-PD2-Pad54)") (class "Default")
      (node (ref "DD1") (pin "54") (pinfunction "PD2_54") (pintype "bidirectional"))
    )
    (net (code "71") (name "unconnected-(R11-Pad1)") (class "Default")
      (node (ref "R11") (pin "1") (pinfunction "1_1") (pintype "passive"))
    )
    (net (code "72") (name "unconnected-(XS1-Pad2)") (class "Default")
      (node (ref "XS1") (pin "2") (pinfunction "2_2") (pintype "passive"))
    )
    (net (code "73") (name "unconnected-(XS1-Pad3)") (class "Default")
      (node (ref "XS1") (pin "3") (pinfunction "3_3") (pintype "passive"))
    )
    (net (code "74") (name "unconnected-(XS1-Pad4)") (class "Default")
      (node (ref "XS1") (pin "4") (pinfunction "4_4") (pintype "passive"))
    )
  )
)
